# GiGa_keyboard.net
KiCad netlist of a schematic drawn in EAGLE
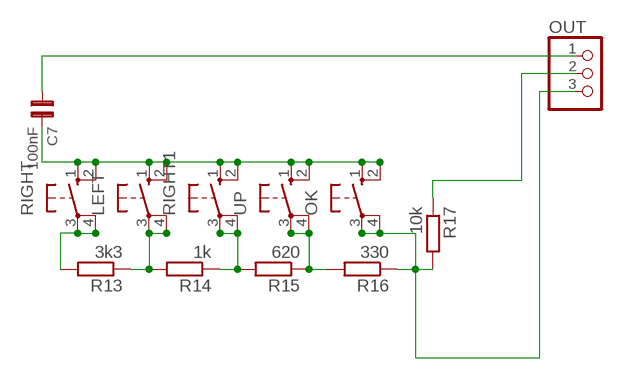
[diagram p0: schematic, sheet 1]

(export (version "E")
  (design (tool "Eeschema 10.0.6"))
  (components
    (comp (ref "C7")
      (value "100nF")
      (footprint "eagle-import:1206")
      (libsource (lib "eagle-import") (part "C1206"))
    )
    (comp (ref "LEFT")
      (value "10-XX")
      (footprint "eagle-import:B3F-10XX")
      (fields (field (name "MPN") "B3F-1000"))
      (libsource (lib "eagle-import") (part "10-XX"))
    )
    (comp (ref "OK")
      (value "10-XX")
      (footprint "eagle-import:B3F-10XX")
      (fields (field (name "MPN") "B3F-1000"))
      (libsource (lib "eagle-import") (part "10-XX"))
    )
    (comp (ref "OUT")
      (value "PINHD-1X3")
      (footprint "eagle-import:1X03")
      (libsource (lib "eagle-import") (part "PINHD-1X3"))
    )
    (comp (ref "R13")
      (value "3k3")
      (footprint "eagle-import:R1206")
      (libsource (lib "eagle-import") (part "R-EU_R1206"))
    )
    (comp (ref "R14")
      (value "1k")
      (footprint "eagle-import:R1206")
      (libsource (lib "eagle-import") (part "R-EU_R1206"))
    )
    (comp (ref "R15")
      (value "620")
      (footprint "eagle-import:R1206")
      (libsource (lib "eagle-import") (part "R-EU_R1206"))
    )
    (comp (ref "R16")
      (value "330")
      (footprint "eagle-import:R1206")
      (libsource (lib "eagle-import") (part "R-EU_R1206"))
    )
    (comp (ref "R17")
      (value "10k")
      (footprint "eagle-import:R1206")
      (libsource (lib "eagle-import") (part "R-EU_R1206"))
    )
    (comp (ref "RIGHT")
      (value "10-XX")
      (footprint "eagle-import:B3F-10XX")
      (fields (field (name "MPN") "B3F-1000"))
      (libsource (lib "eagle-import") (part "10-XX"))
    )
    (comp (ref "RIGHT1")
      (value "10-XX")
      (footprint "eagle-import:B3F-10XX")
      (fields (field (name "MPN") "B3F-1000"))
      (libsource (lib "eagle-import") (part "10-XX"))
    )
    (comp (ref "UP")
      (value "10-XX")
      (footprint "eagle-import:B3F-10XX")
      (fields (field (name "MPN") "B3F-1000"))
      (libsource (lib "eagle-import") (part "10-XX"))
    )
  )
  (nets
    (net (code "1") (name "Net-(C7-Pad1)") (class "Default")
      (node (ref "C7") (pin "1") (pinfunction "1_1") (pintype "passive"))
      (node (ref "OUT") (pin "1") (pinfunction "1_1") (pintype "passive"))
    )
    (net (code "2") (name "Net-(LEFT-P)") (class "Default")
      (node (ref "LEFT") (pin "3") (pinfunction "P_3") (pintype "passive"))
      (node (ref "LEFT") (pin "4") (pinfunction "P1_4") (pintype "passive"))
      (node (ref "R13") (pin "1") (pinfunction "1_1") (pintype "passive"))
      (node (ref "R14") (pin "2") (pinfunction "2_2") (pintype "passive"))
    )
    (net (code "3") (name "Net-(LEFT-S)") (class "Default")
      (node (ref "C7") (pin "2") (pinfunction "2_2") (pintype "passive"))
      (node (ref "LEFT") (pin "1") (pinfunction "S_1") (pintype "passive"))
      (node (ref "LEFT") (pin "2") (pinfunction "S1_2") (pintype "passive"))
      (node (ref "OK") (pin "1") (pinfunction "S_1") (pintype "passive"))
      (node (ref "OK") (pin "2") (pinfunction "S1_2") (pintype "passive"))
      (node (ref "RIGHT") (pin "1") (pinfunction "S_1") (pintype "passive"))
      (node (ref "RIGHT") (pin "2") (pinfunction "S1_2") (pintype "passive"))
      (node (ref "RIGHT1") (pin "1") (pinfunction "S_1") (pintype "passive"))
      (node (ref "RIGHT1") (pin "2") (pinfunction "S1_2") (pintype "passive"))
      (node (ref "UP") (pin "1") (pinfunction "S_1") (pintype "passive"))
      (node (ref "UP") (pin "2") (pinfunction "S1_2") (pintype "passive"))
    )
    (net (code "4") (name "Net-(OK-P)") (class "Default")
      (node (ref "OK") (pin "3") (pinfunction "P_3") (pintype "passive"))
      (node (ref "OK") (pin "4") (pinfunction "P1_4") (pintype "passive"))
      (node (ref "OUT") (pin "3") (pinfunction "3_3") (pintype "passive"))
      (node (ref "R16") (pin "1") (pinfunction "1_1") (pintype "passive"))
      (node (ref "R17") (pin "2") (pinfunction "2_2") (pintype "passive"))
    )
    (net (code "5") (name "Net-(OUT-Pad2)") (class "Default")
      (node (ref "OUT") (pin "2") (pinfunction "2_2") (pintype "passive"))
      (node (ref "R17") (pin "1") (pinfunction "1_1") (pintype "passive"))
    )
    (net (code "6") (name "Net-(RIGHT-P)") (class "Default")
      (node (ref "R13") (pin "2") (pinfunction "2_2") (pintype "passive"))
      (node (ref "RIGHT") (pin "3") (pinfunction "P_3") (pintype "passive"))
      (node (ref "RIGHT") (pin "4") (pinfunction "P1_4") (pintype "passive"))
    )
    (net (code "7") (name "Net-(RIGHT1-P)") (class "Default")
      (node (ref "R14") (pin "1") (pinfunction "1_1") (pintype "passive"))
      (node (ref "R15") (pin "2") (pinfunction "2_2") (pintype "passive"))
      (node (ref "RIGHT1") (pin "3") (pinfunction "P_3") (pintype "passive"))
      (node (ref "RIGHT1") (pin "4") (pinfunction "P1_4") (pintype "passive"))
    )
    (net (code "8") (name "Net-(UP-P)") (class "Default")
      (node (ref "R15") (pin "1") (pinfunction "1_1") (pintype "passive"))
      (node (ref "R16") (pin "2") (pinfunction "2_2") (pintype "passive"))
      (node (ref "UP") (pin "3") (pinfunction "P_3") (pintype "passive"))
      (node (ref "UP") (pin "4") (pinfunction "P1_4") (pintype "passive"))
    )
  )
)
